# transmiter_switch.net
KiCad netlist of a schematic drawn in EAGLE
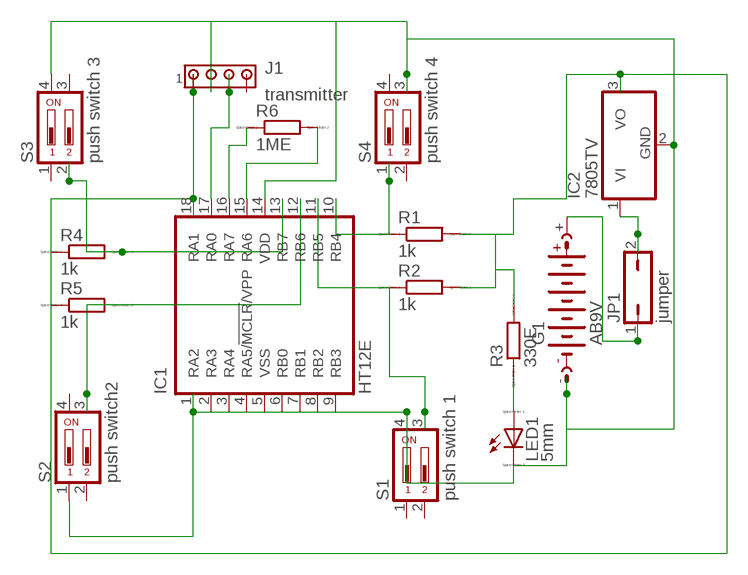
[diagram p0: schematic, sheet 1]

(export (version "E")
  (design (tool "Eeschema 10.0.6"))
  (components
    (comp (ref "G1")
      (value "AB9V")
      (footprint "eagle-import:AB9V")
      (libsource (lib "eagle-import") (part "AB9V"))
    )
    (comp (ref "IC1")
      (value "HT12E")
      (footprint "eagle-import:DIL18")
      (libsource (lib "eagle-import") (part "PIC16F1826/27P"))
    )
    (comp (ref "IC2")
      (value "7805TV")
      (footprint "eagle-import:TO220V")
      (libsource (lib "eagle-import") (part "78TV05"))
    )
    (comp (ref "J1")
      (value "transmitter")
      (footprint "eagle-import:10X04MTA")
      (libsource (lib "eagle-import") (part "MTA04-100"))
    )
    (comp (ref "JP1")
      (value "jumper")
      (footprint "eagle-import:JP1")
      (libsource (lib "eagle-import") (part "JP1Q"))
    )
    (comp (ref "LED1")
      (value "5mm")
      (footprint "eagle-import:LED_LD260")
      (libsource (lib "eagle-import") (part "LED_ELD260"))
    )
    (comp (ref "R1")
      (value "1k")
      (footprint "eagle-import:0204_7")
      (libsource (lib "eagle-import") (part "R0204/7"))
    )
    (comp (ref "R2")
      (value "1k")
      (footprint "eagle-import:0204_7")
      (libsource (lib "eagle-import") (part "R0204/7"))
    )
    (comp (ref "R3")
      (value "330E")
      (footprint "eagle-import:0204_7")
      (libsource (lib "eagle-import") (part "R0204/7"))
    )
    (comp (ref "R4")
      (value "1k")
      (footprint "eagle-import:0204_7")
      (libsource (lib "eagle-import") (part "R0204/7"))
    )
    (comp (ref "R5")
      (value "1k")
      (footprint "eagle-import:0204_7")
      (libsource (lib "eagle-import") (part "R0204/7"))
    )
    (comp (ref "R6")
      (value "1ME")
      (footprint "eagle-import:0204_7")
      (libsource (lib "eagle-import") (part "R0204/7"))
    )
    (comp (ref "S1")
      (value "push switch 1")
      (footprint "eagle-import:DS-02")
      (libsource (lib "eagle-import") (part "DS02"))
    )
    (comp (ref "S2")
      (value "push switch2")
      (footprint "eagle-import:DS-02")
      (libsource (lib "eagle-import") (part "DS02"))
    )
    (comp (ref "S3")
      (value "push switch 3")
      (footprint "eagle-import:DS-02")
      (libsource (lib "eagle-import") (part "DS02"))
    )
    (comp (ref "S4")
      (value "push switch 4")
      (footprint "eagle-import:DS-02")
      (libsource (lib "eagle-import") (part "DS02"))
    )
  )
  (nets
    (net (code "1") (name "Net-(G1-Pad+)") (class "Default")
      (node (ref "G1") (pin "+") (pinfunction "+_+") (pintype "passive"))
      (node (ref "JP1") (pin "1") (pinfunction "1_1") (pintype "passive"))
    )
    (net (code "2") (name "Net-(IC1-RA0)") (class "Default")
      (node (ref "IC1") (pin "17") (pinfunction "RA0_17") (pintype "bidirectional"))
      (node (ref "J1") (pin "3") (pinfunction "3_3") (pintype "passive"))
    )
    (net (code "3") (name "Net-(IC1-RA1)") (class "Default")
      (node (ref "IC1") (pin "18") (pinfunction "RA1_18") (pintype "bidirectional"))
      (node (ref "IC2") (pin "3") (pinfunction "VO_3") (pintype "passive"))
      (node (ref "J1") (pin "1") (pinfunction "1_1") (pintype "passive"))
      (node (ref "R1") (pin "2") (pinfunction "2_2") (pintype "passive"))
      (node (ref "R2") (pin "2") (pinfunction "2_2") (pintype "passive"))
      (node (ref "R3") (pin "2") (pinfunction "2_2") (pintype "passive"))
      (node (ref "R4") (pin "1") (pinfunction "1_1") (pintype "passive"))
      (node (ref "R5") (pin "1") (pinfunction "1_1") (pintype "passive"))
    )
    (net (code "4") (name "Net-(IC1-RA2)") (class "Default")
      (node (ref "G1") (pin "-") (pinfunction "-_-") (pintype "passive"))
      (node (ref "IC1") (pin "1") (pinfunction "RA2_1") (pintype "bidirectional"))
      (node (ref "IC1") (pin "14") (pinfunction "VDD_14") (pintype "power_in"))
      (node (ref "IC1") (pin "2") (pinfunction "RA3_2") (pintype "bidirectional"))
      (node (ref "IC1") (pin "3") (pinfunction "RA4_3") (pintype "bidirectional"))
      (node (ref "IC1") (pin "4") (pinfunction "RA5/~{MCLR}/VPP_4") (pintype "bidirectional"))
      (node (ref "IC1") (pin "5") (pinfunction "VSS_5") (pintype "power_in"))
      (node (ref "IC1") (pin "6") (pinfunction "RB0_6") (pintype "bidirectional"))
      (node (ref "IC1") (pin "7") (pinfunction "RB1_7") (pintype "bidirectional"))
      (node (ref "IC1") (pin "8") (pinfunction "RB2_8") (pintype "bidirectional"))
      (node (ref "IC1") (pin "9") (pinfunction "RB3_9") (pintype "bidirectional"))
      (node (ref "IC2") (pin "2") (pinfunction "GND_2") (pintype "passive"))
      (node (ref "J1") (pin "2") (pinfunction "2_2") (pintype "passive"))
      (node (ref "LED1") (pin "K") (pinfunction "C_K") (pintype "passive"))
      (node (ref "S1") (pin "4") (pinfunction "4_4") (pintype "passive"))
      (node (ref "S2") (pin "1") (pinfunction "1_1") (pintype "passive"))
      (node (ref "S3") (pin "4") (pinfunction "4_4") (pintype "passive"))
      (node (ref "S4") (pin "3") (pinfunction "3_3") (pintype "passive"))
    )
    (net (code "5") (name "Net-(IC1-RA6)") (class "Default")
      (node (ref "IC1") (pin "15") (pinfunction "RA6_15") (pintype "bidirectional"))
      (node (ref "R6") (pin "2") (pinfunction "2_2") (pintype "passive"))
    )
    (net (code "6") (name "Net-(IC1-RA7)") (class "Default")
      (node (ref "IC1") (pin "16") (pinfunction "RA7_16") (pintype "bidirectional"))
      (node (ref "R6") (pin "1") (pinfunction "1_1") (pintype "passive"))
    )
    (net (code "7") (name "Net-(IC1-RB4)") (class "Default")
      (node (ref "IC1") (pin "10") (pinfunction "RB4_10") (pintype "bidirectional"))
      (node (ref "R1") (pin "1") (pinfunction "1_1") (pintype "passive"))
      (node (ref "S4") (pin "1") (pinfunction "1_1") (pintype "passive"))
    )
    (net (code "8") (name "Net-(IC1-RB5)") (class "Default")
      (node (ref "IC1") (pin "11") (pinfunction "RB5_11") (pintype "bidirectional"))
      (node (ref "R2") (pin "1") (pinfunction "1_1") (pintype "passive"))
      (node (ref "S1") (pin "3") (pinfunction "3_3") (pintype "passive"))
    )
    (net (code "9") (name "Net-(IC1-RB6)") (class "Default")
      (node (ref "IC1") (pin "12") (pinfunction "RB6_12") (pintype "bidirectional"))
      (node (ref "R5") (pin "2") (pinfunction "2_2") (pintype "passive"))
      (node (ref "S2") (pin "3") (pinfunction "3_3") (pintype "passive"))
    )
    (net (code "10") (name "Net-(IC1-RB7)") (class "Default")
      (node (ref "IC1") (pin "13") (pinfunction "RB7_13") (pintype "bidirectional"))
      (node (ref "R4") (pin "2") (pinfunction "2_2") (pintype "passive"))
      (node (ref "S3") (pin "2") (pinfunction "2_2") (pintype "passive"))
    )
    (net (code "11") (name "Net-(IC2-VI)") (class "Default")
      (node (ref "IC2") (pin "1") (pinfunction "VI_1") (pintype "input"))
      (node (ref "JP1") (pin "2") (pinfunction "2_2") (pintype "passive"))
    )
    (net (code "12") (name "Net-(LED1-PadA)") (class "Default")
      (node (ref "LED1") (pin "A") (pinfunction "A_A") (pintype "passive"))
      (node (ref "R3") (pin "1") (pinfunction "1_1") (pintype "passive"))
    )
    (net (code "13") (name "unconnected-(J1-Pad4)") (class "Default")
      (node (ref "J1") (pin "4") (pinfunction "4_4") (pintype "passive"))
    )
    (net (code "14") (name "unconnected-(S1-Pad1)") (class "Default")
      (node (ref "S1") (pin "1") (pinfunction "1_1") (pintype "passive"))
    )
    (net (code "15") (name "unconnected-(S1-Pad2)") (class "Default")
      (node (ref "S1") (pin "2") (pinfunction "2_2") (pintype "passive"))
    )
    (net (code "16") (name "unconnected-(S2-Pad2)") (class "Default")
      (node (ref "S2") (pin "2") (pinfunction "2_2") (pintype "passive"))
    )
    (net (code "17") (name "unconnected-(S2-Pad4)") (class "Default")
      (node (ref "S2") (pin "4") (pinfunction "4_4") (pintype "passive"))
    )
    (net (code "18") (name "unconnected-(S3-Pad1)") (class "Default")
      (node (ref "S3") (pin "1") (pinfunction "1_1") (pintype "passive"))
    )
    (net (code "19") (name "unconnected-(S3-Pad3)") (class "Default")
      (node (ref "S3") (pin "3") (pinfunction "3_3") (pintype "passive"))
    )
    (net (code "20") (name "unconnected-(S4-Pad2)") (class "Default")
      (node (ref "S4") (pin "2") (pinfunction "2_2") (pintype "passive"))
    )
    (net (code "21") (name "unconnected-(S4-Pad4)") (class "Default")
      (node (ref "S4") (pin "4") (pinfunction "4_4") (pintype "passive"))
    )
  )
)
